# tiny45-button-2-leds-ext-pullup-power-LE.net
KiCad netlist of a schematic drawn in EAGLE
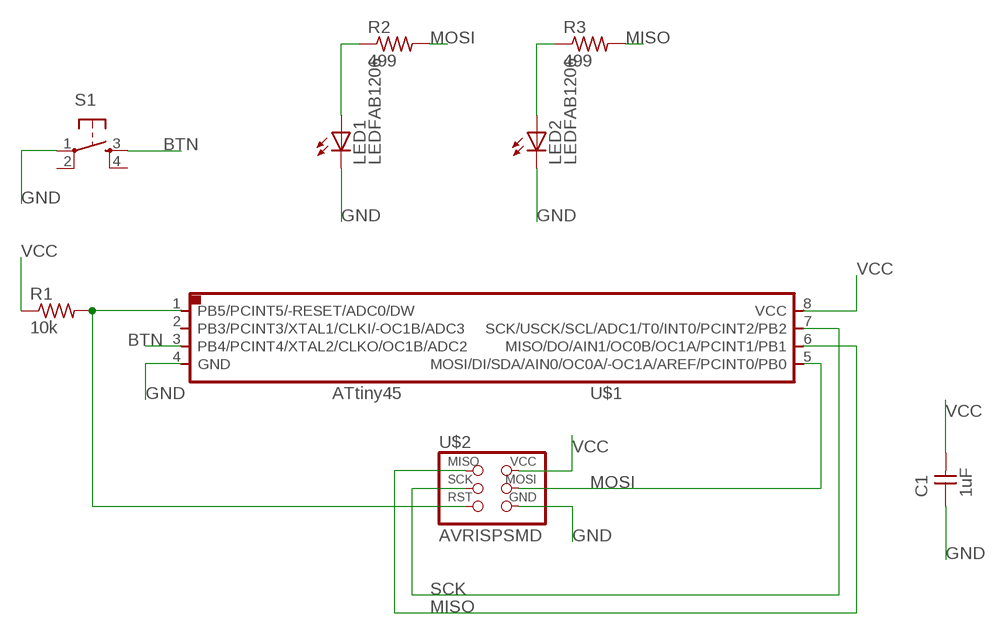
[diagram p0: schematic, sheet 1]

(export (version "E")
  (design (tool "Eeschema 10.0.6"))
  (components
    (comp (ref "C1")
      (value "1uF")
      (footprint "eagle-import:C1206FAB")
      (libsource (lib "eagle-import") (part "CAP-UNPOLARIZEDFAB"))
    )
    (comp (ref "LED1")
      (value "LEDFAB1206")
      (footprint "eagle-import:LED1206FAB")
      (libsource (lib "eagle-import") (part "LEDFAB1206"))
    )
    (comp (ref "LED2")
      (value "LEDFAB1206")
      (footprint "eagle-import:LED1206FAB")
      (libsource (lib "eagle-import") (part "LEDFAB1206"))
    )
    (comp (ref "R1")
      (value "10k")
      (footprint "eagle-import:R1206FAB")
      (libsource (lib "eagle-import") (part "RES-US1206FAB"))
    )
    (comp (ref "R2")
      (value "499")
      (footprint "eagle-import:R1206FAB")
      (libsource (lib "eagle-import") (part "RES-US1206FAB"))
    )
    (comp (ref "R3")
      (value "499")
      (footprint "eagle-import:R1206FAB")
      (libsource (lib "eagle-import") (part "RES-US1206FAB"))
    )
    (comp (ref "S1")
      (value "6MM_SWITCH6MM_SWITCH")
      (footprint "eagle-import:6MM_SWITCH")
      (libsource (lib "eagle-import") (part "6MM_SWITCH6MM_SWITCH"))
    )
    (comp (ref "U$1")
      (value "ATTINY45SI")
      (footprint "eagle-import:SOIC8")
      (libsource (lib "eagle-import") (part "ATTINY45SI"))
    )
    (comp (ref "U$2")
      (value "AVRISPSMD")
      (footprint "eagle-import:2X03SMD")
      (libsource (lib "eagle-import") (part "AVRISPSMD"))
    )
  )
  (nets
    (net (code "1") (name "/BTN") (class "Default")
      (node (ref "S1") (pin "3") (pinfunction "S_3") (pintype "passive"))
      (node (ref "U$1") (pin "3") (pinfunction "PB4/PCINT4/XTAL2/CLKO/OC1B/ADC2_3") (pintype "bidirectional"))
    )
    (net (code "2") (name "/GND") (class "Default")
      (node (ref "C1") (pin "1") (pinfunction "1_1") (pintype "passive"))
      (node (ref "LED1") (pin "2") (pinfunction "C_2") (pintype "passive"))
      (node (ref "LED2") (pin "2") (pinfunction "C_2") (pintype "passive"))
      (node (ref "S1") (pin "1") (pinfunction "P_1") (pintype "passive"))
      (node (ref "U$1") (pin "4") (pinfunction "GND_4") (pintype "bidirectional"))
      (node (ref "U$2") (pin "6") (pinfunction "GND_6") (pintype "passive"))
    )
    (net (code "3") (name "/MISO") (class "Default")
      (node (ref "R3") (pin "2") (pinfunction "2_2") (pintype "passive"))
      (node (ref "U$1") (pin "6") (pinfunction "MISO/DO/AIN1/OC0B/OC1A/PCINT1/PB1_6") (pintype "bidirectional"))
      (node (ref "U$2") (pin "1") (pinfunction "MISO_1") (pintype "passive"))
    )
    (net (code "4") (name "/MOSI") (class "Default")
      (node (ref "R2") (pin "2") (pinfunction "2_2") (pintype "passive"))
      (node (ref "U$1") (pin "5") (pinfunction "MOSI/DI/SDA/AIN0/OC0A/-OC1A/AREF/PCINT0/PB0_5") (pintype "bidirectional"))
      (node (ref "U$2") (pin "4") (pinfunction "MOSI_4") (pintype "passive"))
    )
    (net (code "5") (name "/SCK") (class "Default")
      (node (ref "U$1") (pin "7") (pinfunction "SCK/USCK/SCL/ADC1/T0/INT0/PCINT2/PB2_7") (pintype "bidirectional"))
      (node (ref "U$2") (pin "3") (pinfunction "SCK_3") (pintype "passive"))
    )
    (net (code "6") (name "/VCC") (class "Default")
      (node (ref "C1") (pin "2") (pinfunction "2_2") (pintype "passive"))
      (node (ref "R1") (pin "1") (pinfunction "1_1") (pintype "passive"))
      (node (ref "U$1") (pin "8") (pinfunction "VCC_8") (pintype "bidirectional"))
      (node (ref "U$2") (pin "2") (pinfunction "VCC_2") (pintype "passive"))
    )
    (net (code "7") (name "Net-(LED1-A)") (class "Default")
      (node (ref "LED1") (pin "1") (pinfunction "A_1") (pintype "passive"))
      (node (ref "R2") (pin "1") (pinfunction "1_1") (pintype "passive"))
    )
    (net (code "8") (name "Net-(LED2-A)") (class "Default")
      (node (ref "LED2") (pin "1") (pinfunction "A_1") (pintype "passive"))
      (node (ref "R3") (pin "1") (pinfunction "1_1") (pintype "passive"))
    )
    (net (code "9") (name "Net-(U$1-PB5{slash}PCINT5{slash}-RESET{slash}ADC0{slash}DW)") (class "Default")
      (node (ref "R1") (pin "2") (pinfunction "2_2") (pintype "passive"))
      (node (ref "U$1") (pin "1") (pinfunction "PB5/PCINT5/-RESET/ADC0/DW_1") (pintype "bidirectional"))
      (node (ref "U$2") (pin "5") (pinfunction "RST_5") (pintype "passive"))
    )
    (net (code "10") (name "unconnected-(S1-P1-Pad2)") (class "Default")
      (node (ref "S1") (pin "2") (pinfunction "P1_2") (pintype "passive"))
    )
    (net (code "11") (name "unconnected-(S1-S1-Pad4)") (class "Default")
      (node (ref "S1") (pin "4") (pinfunction "S1_4") (pintype "passive"))
    )
    (net (code "12") (name "unconnected-(U$1-PB3{slash}PCINT3{slash}XTAL1{slash}CLKI{slash}-OC1B{slash}ADC3-Pad2)") (class "Default")
      (node (ref "U$1") (pin "2") (pinfunction "PB3/PCINT3/XTAL1/CLKI/-OC1B/ADC3_2") (pintype "bidirectional"))
    )
  )
)
